# CAN.net
KiCad netlist of a schematic drawn in Altium Designer
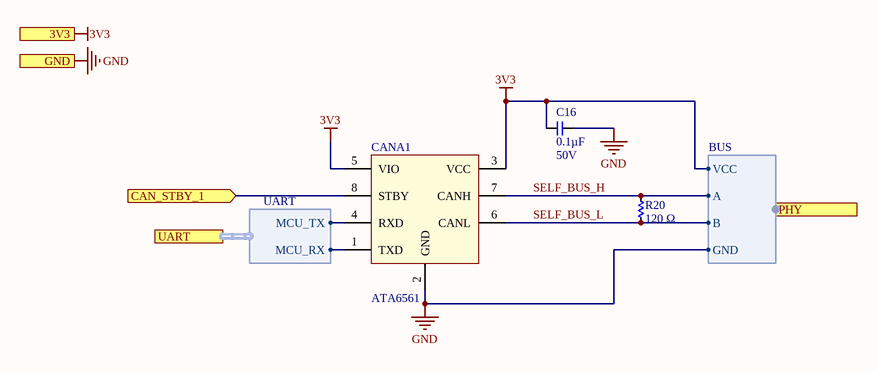
[diagram p0: CAN.SchDoc]

(export (version "E")
  (design (tool "Eeschema 10.0.6"))
  (components
    (comp (ref "C16")
      (value "490-1519-1-ND")
      (footprint "C0603")
      (description "CAP CER 0603 0.1µF X7R 50V 10%")
      (fields
        (field (name "CAPACITANCE (SHORTHAND)") "0.1µF")
        (field (name "MANUFACTURER") "Murata Electronics North America")
        (field (name "RATED VOLTAGE") "50V")
      )
      (libsource (lib "Stanford Student Space Initiative") (part "__template_cap"))
    )
    (comp (ref "CANA1")
      (value "ATA6561")
      (footprint "8SOIC150")
      (description "Atmel CAN Bus Transciever")
      (fields (field (name "SOURCE") "ic_data_converters.SchLib"))
      (libsource (lib "Stanford Student Space Initiative") (part "ATA6561"))
    )
    (comp (ref "R20")
      (value "311-120HRCT-ND")
      (footprint "R0603")
      (description "RES SMD 120 OHM 1% 1/10W 0603")
      (fields
        (field (name "RESISTANCE") "120 Ω")
        (field (name "MANUFACTURER PART NUMBER") "RC0603FR-07120RL")
        (field (name "MANUFACTURER") "Yageo")
      )
      (libsource (lib "Stanford Student Space Initiative") (part "__template_resistor"))
    )
  )
  (nets
    (net (code "3") (name "/CAN_STBY_1") (class "Default")
      (node (ref "CANA1") (pin "8") (pinfunction "STBY_8") (pintype "passive"))
    )
    (net (code "4") (name "/MCU_RX") (class "Default")
      (node (ref "CANA1") (pin "1") (pinfunction "TXD_1") (pintype "passive"))
    )
    (net (code "5") (name "/MCU_TX") (class "Default")
      (node (ref "CANA1") (pin "4") (pinfunction "RXD_4") (pintype "passive"))
    )
    (net (code "6") (name "/SELF_BUS_H") (class "Default")
      (node (ref "CANA1") (pin "7") (pinfunction "CANH_7") (pintype "passive"))
      (node (ref "R20") (pin "2") (pintype "passive"))
    )
    (net (code "7") (name "/SELF_BUS_L") (class "Default")
      (node (ref "CANA1") (pin "6") (pinfunction "CANL_6") (pintype "passive"))
      (node (ref "R20") (pin "1") (pintype "passive"))
    )
    (net (code "10") (name "3V3") (class "Default")
      (node (ref "C16") (pin "2") (pintype "passive"))
      (node (ref "CANA1") (pin "3") (pinfunction "VCC_3") (pintype "passive"))
      (node (ref "CANA1") (pin "5") (pinfunction "VIO_5") (pintype "passive"))
    )
    (net (code "11") (name "GND") (class "Default")
      (node (ref "C16") (pin "1") (pintype "passive"))
      (node (ref "CANA1") (pin "2") (pinfunction "GND_2") (pintype "passive"))
    )
  )
)
